# Power_Generation_-_LDO.net
KiCad netlist of a schematic drawn in Altium Designer
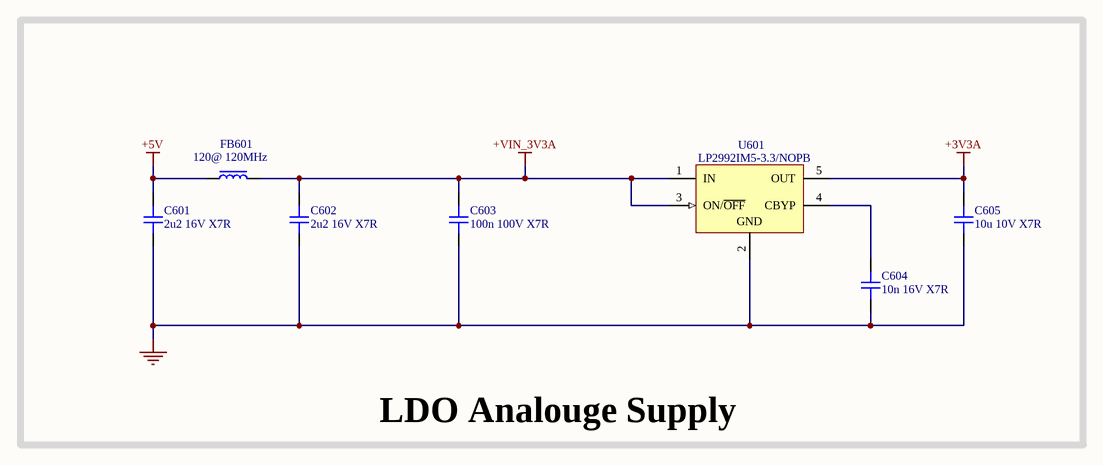
[diagram p0: Power Generation - LDO.SchDoc]

(export (version "E")
  (design (tool "Eeschema 10.0.6"))
  (components
    (comp (ref "C601")
      (value "2u2 16V X7R")
      (footprint "CAP_0805")
      (description "Capacitor SMD 0805")
      (fields
        (field (name "MANUFACTURER") "HRE")
        (field (name "MANUFACTURER PART NUMBER") "CGA0805X7R225K160MT")
      )
      (libsource (lib "Schematic-Lib-PhilsLab") (part "CAP_0805"))
    )
    (comp (ref "C602")
      (value "2u2 16V X7R")
      (footprint "CAP_0805")
      (description "Capacitor SMD 0805")
      (fields
        (field (name "MANUFACTURER") "HRE")
        (field (name "MANUFACTURER PART NUMBER") "CGA0805X7R225K160MT")
      )
      (libsource (lib "Schematic-Lib-PhilsLab") (part "CAP_0805"))
    )
    (comp (ref "C603")
      (value "100n 100V X7R")
      (footprint "CAP_0805")
      (description "Capacitor SMD 0805")
      (fields
        (field (name "MANUFACTURER") "YAGEO")
        (field (name "MANUFACTURER PART NUMBER") "CC0805JRX7R7BB104")
      )
      (libsource (lib "Schematic-Lib-PhilsLab") (part "CAP_0805"))
    )
    (comp (ref "C604")
      (value "10n 16V X7R")
      (footprint "CAP_0603")
      (description "Capacitor SMD 0603")
      (fields
        (field (name "MANUFACTURER") "YAGEO")
        (field (name "MANUFACTURER PART NUMBER") "CC0603JRX7R7BB103")
      )
      (libsource (lib "Schematic-Lib-PhilsLab") (part "CAP_0603"))
    )
    (comp (ref "C605")
      (value "10u 10V X7R")
      (footprint "CAP_0805")
      (description "Capacitor SMD 0805")
      (fields
        (field (name "MANUFACTURER") "Murata Electronics")
        (field (name "MANUFACTURER PART NUMBER") "GCM21BR71A106KE22K")
      )
      (libsource (lib "Schematic-Lib-PhilsLab") (part "CAP_0805"))
    )
    (comp (ref "FB601")
      (value "120@ 120MHz")
      (footprint "FB_0805")
      (description "Ferrite Bead SMD 0805")
      (fields
        (field (name "MANUFACTURER") "Murata Electronics")
        (field (name "MANUFACTURER PART NUMBER") "BLM21AG121SN1D")
      )
      (libsource (lib "Schematic-Lib-PhilsLab") (part "FB_0805"))
    )
    (comp (ref "U601")
      (value "LP2992IM5-3.3/NOPB")
      (footprint "DBV0005A_L")
      (description "Micropower 250 mA Low-Noise Ultra Low-Dropout Regulator, 5-pin SOT-23, Pb-Free")
      (fields (field (name "MANUFACTURER") "Texas Instruments"))
      (libsource (lib "Altium Content Vault") (part "PM-REG-LP2985-SOT5"))
    )
  )
  (nets
    (net (code "1") (name "+3V3A") (class "Default")
      (node (ref "C605") (pin "1") (pinfunction "1_1") (pintype "passive"))
      (node (ref "U601") (pin "5") (pinfunction "OUT_5") (pintype "power_in"))
    )
    (net (code "2") (name "+5V") (class "Default")
      (node (ref "C601") (pin "1") (pinfunction "1_1") (pintype "passive"))
      (node (ref "FB601") (pin "1") (pinfunction "1_1") (pintype "passive"))
    )
    (net (code "3") (name "+VIN_3V3A") (class "Default")
      (node (ref "C602") (pin "1") (pinfunction "1_1") (pintype "passive"))
      (node (ref "C603") (pin "1") (pinfunction "1_1") (pintype "passive"))
      (node (ref "FB601") (pin "2") (pinfunction "2_2") (pintype "passive"))
      (node (ref "U601") (pin "1") (pinfunction "IN_1") (pintype "power_in"))
      (node (ref "U601") (pin "3") (pinfunction "ON/~{OFF}_3") (pintype "input"))
    )
    (net (code "4") (name "GND") (class "Default")
      (node (ref "C601") (pin "2") (pinfunction "2_2") (pintype "passive"))
      (node (ref "C602") (pin "2") (pinfunction "2_2") (pintype "passive"))
      (node (ref "C603") (pin "2") (pinfunction "2_2") (pintype "passive"))
      (node (ref "C604") (pin "1") (pinfunction "1_1") (pintype "passive"))
      (node (ref "C605") (pin "2") (pinfunction "2_2") (pintype "passive"))
      (node (ref "U601") (pin "2") (pinfunction "GND_2") (pintype "power_in"))
    )
    (net (code "5") (name "Net-(U601-CBYP)") (class "Default")
      (node (ref "C604") (pin "2") (pinfunction "2_2") (pintype "passive"))
      (node (ref "U601") (pin "4") (pinfunction "CBYP_4") (pintype "passive"))
    )
  )
)
